# batt_protector.net
KiCad netlist of a schematic drawn in EAGLE
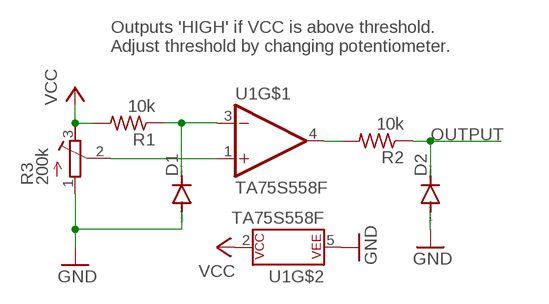
[diagram p0: schematic, sheet 1]

(export (version "E")
  (design (tool "Eeschema 10.0.6"))
  (components
    (comp (ref "D1")
      (value "DIODE-SOD323-R")
      (footprint "eagle-import:SOD323-R")
      (libsource (lib "eagle-import") (part "DIODE-SOD323-R"))
    )
    (comp (ref "D2")
      (value "DIODE-SOD323-R")
      (footprint "eagle-import:SOD323-R")
      (libsource (lib "eagle-import") (part "DIODE-SOD323-R"))
    )
    (comp (ref "R1")
      (value "10k")
      (footprint "eagle-import:R0603")
      (libsource (lib "eagle-import") (part "R-US_R0603"))
    )
    (comp (ref "R2")
      (value "10k")
      (footprint "eagle-import:R0603")
      (libsource (lib "eagle-import") (part "R-US_R0603"))
    )
    (comp (ref "R3")
      (value "200k")
      (footprint "eagle-import:RTRIM64P")
      (libsource (lib "eagle-import") (part "R-TRIMM64P"))
    )
    (comp (ref "U1")
      (value "TA75S558F")
      (footprint "eagle-import:SOTFL95P275X130-5N")
      (libsource (lib "eagle-import") (part "TA75S558F"))
    )
  )
  (nets
    (net (code "1") (name "/OUTPUT") (class "Default")
      (node (ref "D2") (pin "C") (pinfunction "C_C") (pintype "passive"))
      (node (ref "R2") (pin "1") (pinfunction "1_1") (pintype "passive"))
    )
    (net (code "2") (name "GND") (class "Default")
      (node (ref "D1") (pin "A") (pinfunction "A_A") (pintype "passive"))
      (node (ref "D2") (pin "A") (pinfunction "A_A") (pintype "passive"))
      (node (ref "R3") (pin "1") (pinfunction "A_1") (pintype "passive"))
      (node (ref "U1") (pin "5") (pinfunction "P$V-_5") (pintype "bidirectional"))
    )
    (net (code "3") (name "Net-(R3-S)") (class "Default")
      (node (ref "R3") (pin "2") (pinfunction "S_2") (pintype "passive"))
      (node (ref "U1") (pin "1") (pinfunction "+IN_1") (pintype "input"))
    )
    (net (code "4") (name "Net-(U1A--IN)") (class "Default")
      (node (ref "D1") (pin "C") (pinfunction "C_C") (pintype "passive"))
      (node (ref "R1") (pin "1") (pinfunction "1_1") (pintype "passive"))
      (node (ref "U1") (pin "3") (pinfunction "-IN_3") (pintype "input"))
    )
    (net (code "5") (name "Net-(U1A-OUT)") (class "Default")
      (node (ref "R2") (pin "2") (pinfunction "2_2") (pintype "passive"))
      (node (ref "U1") (pin "4") (pinfunction "OUT_4") (pintype "output"))
    )
    (net (code "6") (name "VCC") (class "Default")
      (node (ref "R1") (pin "2") (pinfunction "2_2") (pintype "passive"))
      (node (ref "R3") (pin "3") (pinfunction "E_3") (pintype "passive"))
      (node (ref "U1") (pin "2") (pinfunction "P$V+_2") (pintype "bidirectional"))
    )
  )
)
